# untitled.net
KiCad netlist of a schematic drawn in EAGLE
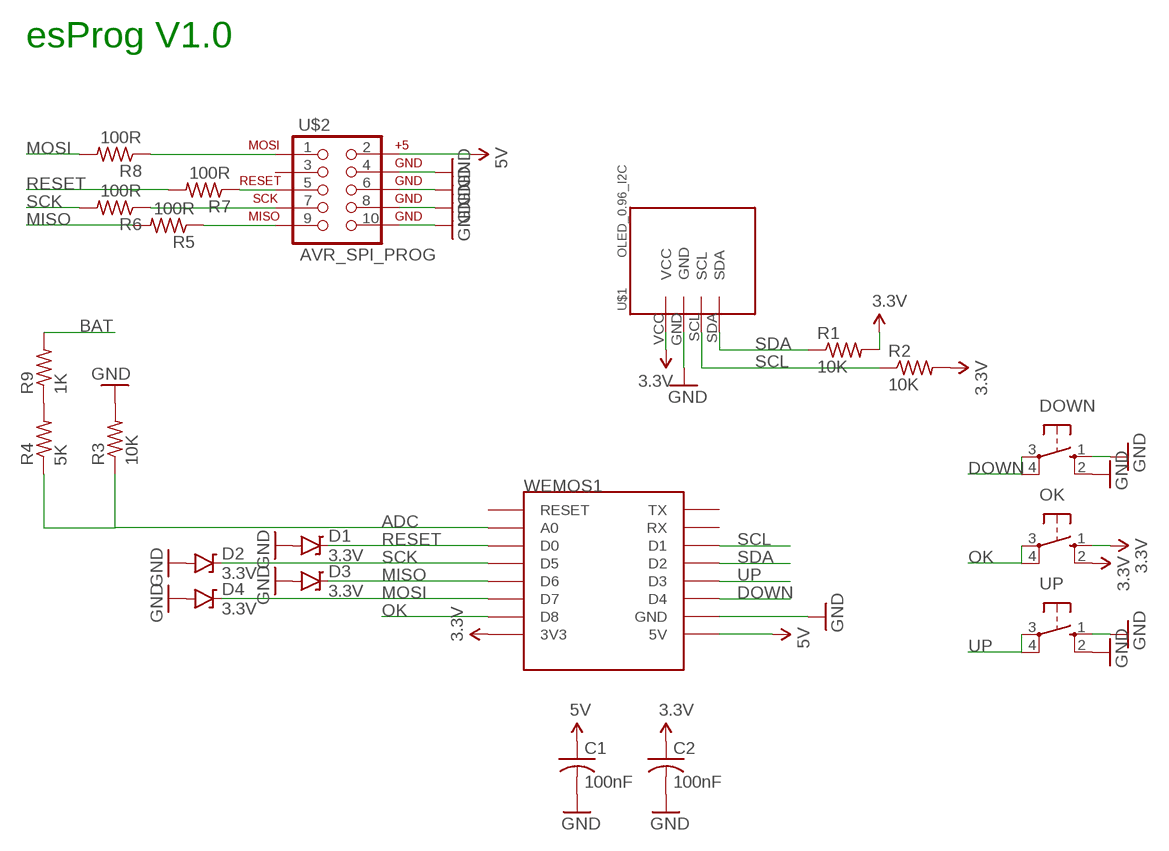
[diagram p0: schematic, sheet 1]

(export (version "E")
  (design (tool "Eeschema 10.0.6"))
  (components
    (comp (ref "C1")
      (value "100nF")
      (footprint "eagle-import:C0805K")
      (libsource (lib "eagle-import") (part "C-USC0805K"))
    )
    (comp (ref "C2")
      (value "100nF")
      (footprint "eagle-import:C0805K")
      (libsource (lib "eagle-import") (part "C-USC0805K"))
    )
    (comp (ref "D1")
      (value "3.3V")
      (footprint "eagle-import:SOD-323")
      (libsource (lib "eagle-import") (part "DIODE-ZENER3.3V"))
    )
    (comp (ref "D2")
      (value "3.3V")
      (footprint "eagle-import:SOD-323")
      (libsource (lib "eagle-import") (part "DIODE-ZENER3.3V"))
    )
    (comp (ref "D3")
      (value "3.3V")
      (footprint "eagle-import:SOD-323")
      (libsource (lib "eagle-import") (part "DIODE-ZENER3.3V"))
    )
    (comp (ref "D4")
      (value "3.3V")
      (footprint "eagle-import:SOD-323")
      (libsource (lib "eagle-import") (part "DIODE-ZENER3.3V"))
    )
    (comp (ref "DOWN")
      (value "10-XX")
      (footprint "eagle-import:B3F-10XX")
      (fields (field (name "MPN") "B3F-1000"))
      (libsource (lib "eagle-import") (part "10-XX"))
    )
    (comp (ref "OK")
      (value "10-XX")
      (footprint "eagle-import:B3F-10XX")
      (fields (field (name "MPN") "B3F-1000"))
      (libsource (lib "eagle-import") (part "10-XX"))
    )
    (comp (ref "R1")
      (value "10K")
      (footprint "eagle-import:R0805")
      (libsource (lib "eagle-import") (part "R-US_R0805"))
    )
    (comp (ref "R2")
      (value "10K")
      (footprint "eagle-import:R0805")
      (libsource (lib "eagle-import") (part "R-US_R0805"))
    )
    (comp (ref "R3")
      (value "10K")
      (footprint "eagle-import:R0805")
      (libsource (lib "eagle-import") (part "R-US_R0805"))
    )
    (comp (ref "R4")
      (value "5K")
      (footprint "eagle-import:R0805")
      (libsource (lib "eagle-import") (part "R-US_R0805"))
    )
    (comp (ref "R5")
      (value "100R")
      (footprint "eagle-import:R0805")
      (libsource (lib "eagle-import") (part "R-US_R0805"))
    )
    (comp (ref "R6")
      (value "100R")
      (footprint "eagle-import:R0805")
      (libsource (lib "eagle-import") (part "R-US_R0805"))
    )
    (comp (ref "R7")
      (value "100R")
      (footprint "eagle-import:R0805")
      (libsource (lib "eagle-import") (part "R-US_R0805"))
    )
    (comp (ref "R8")
      (value "100R")
      (footprint "eagle-import:R0805")
      (libsource (lib "eagle-import") (part "R-US_R0805"))
    )
    (comp (ref "R9")
      (value "1K")
      (footprint "eagle-import:R0805")
      (libsource (lib "eagle-import") (part "R-US_R0805"))
    )
    (comp (ref "U$1")
      (value "OLED_0.96_I2C")
      (footprint "eagle-import:OLED_0.96_I2C")
      (libsource (lib "eagle-import") (part "OLED_0.96_I2C"))
    )
    (comp (ref "U$2")
      (value "AVR_SPI_PROG")
      (footprint "eagle-import:AVR_ICSP")
      (libsource (lib "eagle-import") (part "AVR_SPI_PROG"))
    )
    (comp (ref "UP")
      (value "10-XX")
      (footprint "eagle-import:B3F-10XX")
      (fields (field (name "MPN") "B3F-1000"))
      (libsource (lib "eagle-import") (part "10-XX"))
    )
    (comp (ref "WEMOS1")
      (value "WEMOS-D1-MINI")
      (footprint "eagle-import:WEMOS-D1-MINI")
      (libsource (lib "eagle-import") (part "WEMOS-D1-MINI"))
    )
  )
  (nets
    (net (code "1") (name "/ADC") (class "Default")
      (node (ref "R3") (pin "1") (pinfunction "1_1") (pintype "passive"))
      (node (ref "R4") (pin "1") (pinfunction "1_1") (pintype "passive"))
      (node (ref "WEMOS1") (pin "A0") (pinfunction "A0_A0") (pintype "bidirectional"))
    )
    (net (code "2") (name "/BAT") (class "Default")
      (node (ref "R9") (pin "2") (pinfunction "2_2") (pintype "passive"))
    )
    (net (code "3") (name "/DOWN") (class "Default")
      (node (ref "DOWN") (pin "3") (pinfunction "P_3") (pintype "passive"))
      (node (ref "DOWN") (pin "4") (pinfunction "P1_4") (pintype "passive"))
      (node (ref "WEMOS1") (pin "D4") (pinfunction "D4_D4") (pintype "bidirectional"))
    )
    (net (code "4") (name "/MISO") (class "Default")
      (node (ref "D3") (pin "C") (pinfunction "C_C") (pintype "passive"))
      (node (ref "R5") (pin "2") (pinfunction "2_2") (pintype "passive"))
      (node (ref "WEMOS1") (pin "D6") (pinfunction "D6_D6") (pintype "bidirectional"))
    )
    (net (code "5") (name "/MOSI") (class "Default")
      (node (ref "D4") (pin "C") (pinfunction "C_C") (pintype "passive"))
      (node (ref "R8") (pin "2") (pinfunction "2_2") (pintype "passive"))
      (node (ref "WEMOS1") (pin "D7") (pinfunction "D7_D7") (pintype "bidirectional"))
    )
    (net (code "6") (name "/OK") (class "Default")
      (node (ref "OK") (pin "3") (pinfunction "P_3") (pintype "passive"))
      (node (ref "OK") (pin "4") (pinfunction "P1_4") (pintype "passive"))
      (node (ref "WEMOS1") (pin "D8") (pinfunction "D8_D8") (pintype "bidirectional"))
    )
    (net (code "7") (name "/RESET") (class "Default")
      (node (ref "D1") (pin "C") (pinfunction "C_C") (pintype "passive"))
      (node (ref "R7") (pin "2") (pinfunction "2_2") (pintype "passive"))
      (node (ref "WEMOS1") (pin "D0") (pinfunction "D0_D0") (pintype "bidirectional"))
    )
    (net (code "8") (name "/SCK") (class "Default")
      (node (ref "D2") (pin "C") (pinfunction "C_C") (pintype "passive"))
      (node (ref "R6") (pin "2") (pinfunction "2_2") (pintype "passive"))
      (node (ref "WEMOS1") (pin "D5") (pinfunction "D5_D5") (pintype "bidirectional"))
    )
    (net (code "9") (name "/SCL") (class "Default")
      (node (ref "R2") (pin "1") (pinfunction "1_1") (pintype "passive"))
      (node (ref "U$1") (pin "SCL") (pinfunction "SCL_SCL") (pintype "bidirectional"))
      (node (ref "WEMOS1") (pin "D1") (pinfunction "D1_D1") (pintype "bidirectional"))
    )
    (net (code "10") (name "/SDA") (class "Default")
      (node (ref "R1") (pin "1") (pinfunction "1_1") (pintype "passive"))
      (node (ref "U$1") (pin "SDA") (pinfunction "SDA_SDA") (pintype "bidirectional"))
      (node (ref "WEMOS1") (pin "D2") (pinfunction "D2_D2") (pintype "bidirectional"))
    )
    (net (code "11") (name "/UP") (class "Default")
      (node (ref "UP") (pin "3") (pinfunction "P_3") (pintype "passive"))
      (node (ref "UP") (pin "4") (pinfunction "P1_4") (pintype "passive"))
      (node (ref "WEMOS1") (pin "D3") (pinfunction "D3_D3") (pintype "bidirectional"))
    )
    (net (code "12") (name "3.3V") (class "Default")
      (node (ref "C2") (pin "1") (pinfunction "1_1") (pintype "passive"))
      (node (ref "OK") (pin "1") (pinfunction "S_1") (pintype "passive"))
      (node (ref "OK") (pin "2") (pinfunction "S1_2") (pintype "passive"))
      (node (ref "R1") (pin "2") (pinfunction "2_2") (pintype "passive"))
      (node (ref "R2") (pin "2") (pinfunction "2_2") (pintype "passive"))
      (node (ref "U$1") (pin "VCC") (pinfunction "VCC_VCC") (pintype "bidirectional"))
      (node (ref "WEMOS1") (pin "3V3") (pinfunction "3V3_3V3") (pintype "bidirectional"))
    )
    (net (code "13") (name "5V") (class "Default")
      (node (ref "C1") (pin "1") (pinfunction "1_1") (pintype "passive"))
      (node (ref "U$2") (pin "2") (pinfunction "2_2") (pintype "passive"))
      (node (ref "WEMOS1") (pin "5V") (pinfunction "5V_5V") (pintype "bidirectional"))
    )
    (net (code "14") (name "GND") (class "Default")
      (node (ref "C1") (pin "2") (pinfunction "2_2") (pintype "passive"))
      (node (ref "C2") (pin "2") (pinfunction "2_2") (pintype "passive"))
      (node (ref "D1") (pin "A") (pinfunction "A_A") (pintype "passive"))
      (node (ref "D2") (pin "A") (pinfunction "A_A") (pintype "passive"))
      (node (ref "D3") (pin "A") (pinfunction "A_A") (pintype "passive"))
      (node (ref "D4") (pin "A") (pinfunction "A_A") (pintype "passive"))
      (node (ref "DOWN") (pin "1") (pinfunction "S_1") (pintype "passive"))
      (node (ref "DOWN") (pin "2") (pinfunction "S1_2") (pintype "passive"))
      (node (ref "R3") (pin "2") (pinfunction "2_2") (pintype "passive"))
      (node (ref "U$1") (pin "GND") (pinfunction "GND_GND") (pintype "bidirectional"))
      (node (ref "U$2") (pin "10") (pinfunction "10_10") (pintype "passive"))
      (node (ref "U$2") (pin "4") (pinfunction "4_4") (pintype "passive"))
      (node (ref "U$2") (pin "6") (pinfunction "6_6") (pintype "passive"))
      (node (ref "U$2") (pin "8") (pinfunction "8_8") (pintype "passive"))
      (node (ref "UP") (pin "1") (pinfunction "S_1") (pintype "passive"))
      (node (ref "UP") (pin "2") (pinfunction "S1_2") (pintype "passive"))
      (node (ref "WEMOS1") (pin "GND") (pinfunction "GND_GND") (pintype "bidirectional"))
    )
    (net (code "15") (name "Net-(R4-Pad2)") (class "Default")
      (node (ref "R4") (pin "2") (pinfunction "2_2") (pintype "passive"))
      (node (ref "R9") (pin "1") (pinfunction "1_1") (pintype "passive"))
    )
    (net (code "16") (name "Net-(R5-Pad1)") (class "Default")
      (node (ref "R5") (pin "1") (pinfunction "1_1") (pintype "passive"))
      (node (ref "U$2") (pin "9") (pinfunction "9_9") (pintype "passive"))
    )
    (net (code "17") (name "Net-(R6-Pad1)") (class "Default")
      (node (ref "R6") (pin "1") (pinfunction "1_1") (pintype "passive"))
      (node (ref "U$2") (pin "7") (pinfunction "7_7") (pintype "passive"))
    )
    (net (code "18") (name "Net-(R7-Pad1)") (class "Default")
      (node (ref "R7") (pin "1") (pinfunction "1_1") (pintype "passive"))
      (node (ref "U$2") (pin "5") (pinfunction "5_5") (pintype "passive"))
    )
    (net (code "19") (name "Net-(R8-Pad1)") (class "Default")
      (node (ref "R8") (pin "1") (pinfunction "1_1") (pintype "passive"))
      (node (ref "U$2") (pin "1") (pinfunction "1_1") (pintype "passive"))
    )
    (net (code "20") (name "unconnected-(U$2-Pad3)") (class "Default")
      (node (ref "U$2") (pin "3") (pinfunction "3_3") (pintype "passive"))
    )
    (net (code "21") (name "unconnected-(WEMOS1-PadRESET)") (class "Default")
      (node (ref "WEMOS1") (pin "RESET") (pinfunction "RESET_RESET") (pintype "bidirectional"))
    )
    (net (code "22") (name "unconnected-(WEMOS1-PadRX)") (class "Default")
      (node (ref "WEMOS1") (pin "RX") (pinfunction "RX_RX") (pintype "bidirectional"))
    )
    (net (code "23") (name "unconnected-(WEMOS1-PadTX)") (class "Default")
      (node (ref "WEMOS1") (pin "TX") (pinfunction "TX_TX") (pintype "bidirectional"))
    )
  )
)
